# USB.net
KiCad netlist of a schematic drawn in Altium Designer
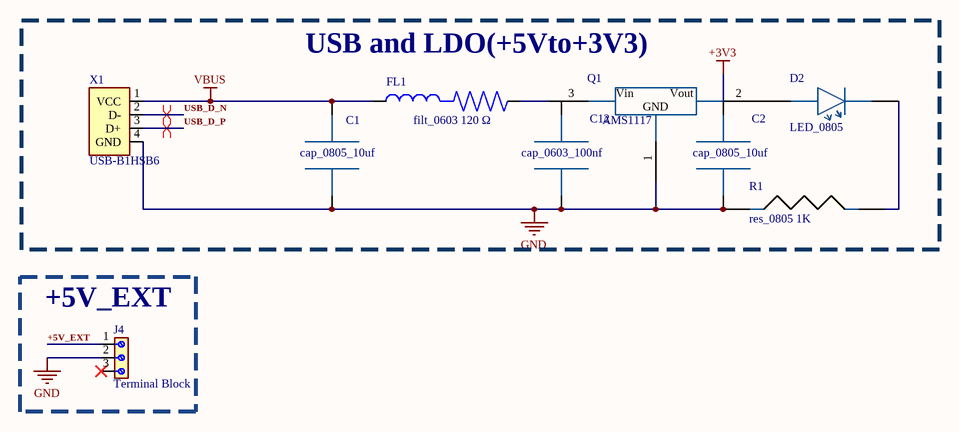
[diagram p0: USB.SchDoc]

(export (version "E")
  (design (tool "Eeschema 10.0.6"))
  (components
    (comp (ref "C1")
      (value "cap_0805_10uf")
      (footprint "capa0805")
      (fields (field (name "MFR") "Samsung Electro-Mechanics") (field (name "MFR PART") "CL21A106KAYNNNE"))
      (libsource (lib "STM32") (part "cap_0805_10uf"))
    )
    (comp (ref "C2")
      (value "cap_0805_10uf")
      (footprint "capa0805")
      (fields (field (name "MFR") "Samsung Electro-Mechanics") (field (name "MFR PART") "CL21A106KAYNNNE"))
      (libsource (lib "STM32") (part "cap_0805_10uf"))
    )
    (comp (ref "C12")
      (value "cap_0603_100nf")
      (footprint "capa0805")
      (fields (field (name "MFR") "Samsung Electro-Mechanics") (field (name "MFR PART") "CL10B104KB8NNNC"))
      (libsource (lib "Schlib final") (part "cap_0603_100nf"))
    )
    (comp (ref "D2")
      (value "LED_0805")
      (footprint "LED_0805")
      (fields (field (name "MFR") "YONGYUTAI") (field (name "MFR PART") "YLED0805R"))
      (libsource (lib "Schlib final") (part "LED_0805"))
    )
    (comp (ref "FL1")
      (value "filt_0603 120 Ω")
      (footprint "BEADC1608X95N")
      (fields (field (name "MFR") "muRata") (field (name "MFR PART") "BLM18EG121SH1D"))
      (libsource (lib "STM32") (part "filt_0603"))
    )
    (comp (ref "J4")
      (value "Terminal Block")
      (footprint "691216710003")
      (fields (field (name "MFR") "MAX") (field (name "MFR PART") "MX126-5.0-02P-GN01-Cu-S-A"))
      (libsource (lib "Schlib final") (part "Terminal Block"))
    )
    (comp (ref "Q1")
      (value "AMS1117")
      (footprint "AMS1117")
      (fields (field (name "MFR") "Advanced Monolithic Systems") (field (name "MFR PART") "AMS1117-3.3"))
      (libsource (lib "STM32") (part "AMS1117"))
    )
    (comp (ref "R1")
      (value "res_0805 1K")
      (footprint "Res_0805")
      (fields (field (name "MFR") "FOJAN") (field (name "MFR PART") "FRC0805F1001TS"))
      (libsource (lib "STM32") (part "res_0805"))
    )
    (comp (ref "X1")
      (value "USB-B1HSB6")
      (footprint "USB-B1HSB6")
      (fields (field (name "MFR") "On-Shore Tech"))
      (libsource (lib "STM32") (part "USB-B1HSB6"))
    )
  )
  (nets
    (net (code "1") (name "+3V3") (class "Default")
      (node (ref "C2") (pin "2") (pinfunction "2_2") (pintype "passive"))
    )
    (net (code "2") (name "/+5V_EXT") (class "Default")
      (node (ref "J4") (pin "1") (pinfunction "1_1") (pintype "passive"))
    )
    (net (code "3") (name "/USB_D_N") (class "Default")
      (node (ref "X1") (pin "2") (pinfunction "D-_2") (pintype "bidirectional"))
    )
    (net (code "4") (name "/USB_D_P") (class "Default")
      (node (ref "X1") (pin "3") (pinfunction "D+_3") (pintype "bidirectional"))
    )
    (net (code "5") (name "GND") (class "Default")
      (node (ref "C1") (pin "1") (pinfunction "1_1") (pintype "passive"))
      (node (ref "C12") (pin "1") (pinfunction "1_1") (pintype "passive"))
      (node (ref "C2") (pin "1") (pinfunction "1_1") (pintype "passive"))
      (node (ref "J4") (pin "2") (pinfunction "2_2") (pintype "passive"))
      (node (ref "Q1") (pin "1") (pinfunction "1_1") (pintype "passive"))
      (node (ref "R1") (pin "1") (pinfunction "1_1") (pintype "passive"))
      (node (ref "X1") (pin "4") (pinfunction "GND_4") (pintype "power_in"))
    )
    (net (code "6") (name "Net-(D2-Pad1)") (class "Default")
      (node (ref "D2") (pin "1") (pinfunction "1_1") (pintype "passive"))
      (node (ref "Q1") (pin "2") (pinfunction "2_2") (pintype "passive"))
    )
    (net (code "7") (name "Net-(D2-Pad2)") (class "Default")
      (node (ref "D2") (pin "2") (pinfunction "2_2") (pintype "passive"))
      (node (ref "R1") (pin "2") (pinfunction "2_2") (pintype "passive"))
    )
    (net (code "8") (name "Net-(FL1-Pad2)") (class "Default")
      (node (ref "FL1") (pin "2") (pinfunction "2_2") (pintype "passive"))
      (node (ref "Q1") (pin "3") (pinfunction "3_3") (pintype "passive"))
    )
    (net (code "9") (name "VBUS") (class "Default")
      (node (ref "C1") (pin "2") (pinfunction "2_2") (pintype "passive"))
      (node (ref "FL1") (pin "1") (pinfunction "1_1") (pintype "passive"))
      (node (ref "X1") (pin "1") (pinfunction "VCC_1") (pintype "power_in"))
    )
    (net (code "10") (name "unconnected-(C12-Pad2)") (class "Default")
      (node (ref "C12") (pin "2") (pinfunction "2_2") (pintype "passive"))
    )
    (net (code "11") (name "unconnected-(J4-Pad3)") (class "Default")
      (node (ref "J4") (pin "3") (pinfunction "3_3") (pintype "passive+no_connect"))
    )
  )
)
